# test3.net
KiCad netlist of a schematic drawn in Altium Designer
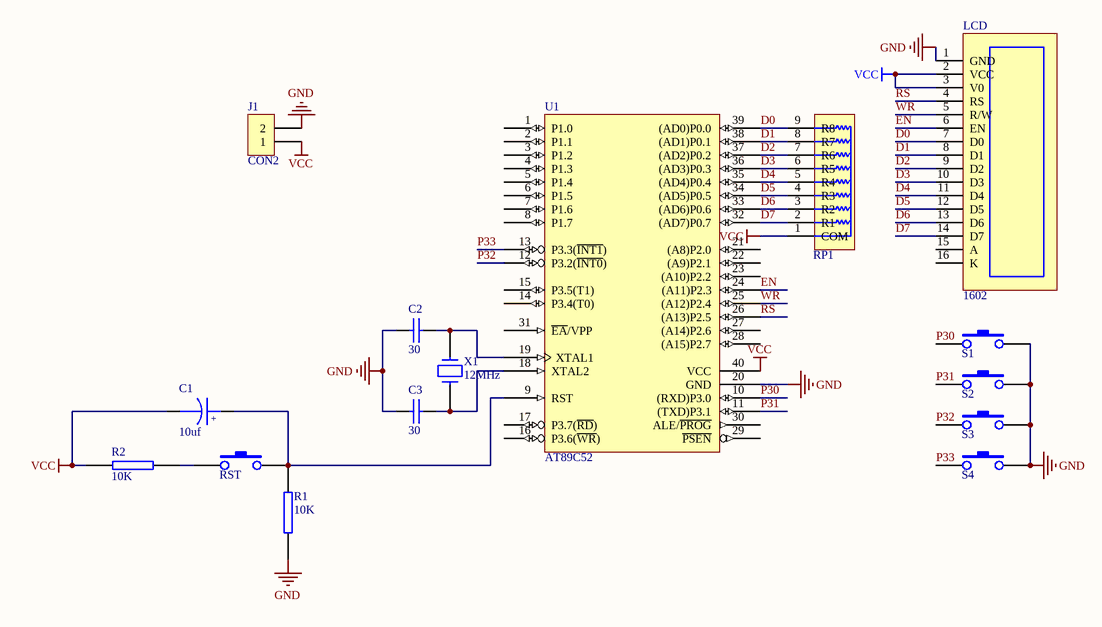
[diagram p0: test3.SchDoc]

(export (version "E")
  (design (tool "Eeschema 10.0.6"))
  (components
    (comp (ref "C1")
      (value "10uf")
      (footprint "C_SMT-5*5")
      (description "Capacitor")
      (libsource (lib "xinweidz") (part "电解电容"))
    )
    (comp (ref "C2")
      (value "30")
      (footprint "C0805")
      (description "Capacitor")
      (libsource (lib "*") (part "CAP"))
    )
    (comp (ref "C3")
      (value "30")
      (footprint "C0805")
      (description "Capacitor")
      (libsource (lib "*") (part "CAP"))
    )
    (comp (ref "J1")
      (value "CON2")
      (footprint "TC2")
      (description "Connector")
      (libsource (lib "51单片机最小系统.PcbDoc") (part "CON2"))
    )
    (comp (ref "LCD") (value "1602") (footprint "LCD1602") (libsource (lib "*") (part "LCM1602")))
    (comp (ref "R1") (value "10K") (footprint "C0805") (libsource (lib "*") (part "RES2")))
    (comp (ref "R2") (value "10K") (footprint "C0805") (libsource (lib "*") (part "RES2")))
    (comp (ref "RP1") (value "103") (footprint "R-9PIN") (libsource (lib "*") (part "RP8")))
    (comp (ref "RST")
      (value "SW-PB")
      (footprint "ANJIAN")
      (libsource (lib "51单片机最小系统.PcbDoc") (part "SW-PB"))
    )
    (comp (ref "S1") (value "SW-PB") (footprint "ANJIAN") (libsource (lib "51单片机最小系统.PcbDoc") (part "SW-PB")))
    (comp (ref "S2") (value "SW-PB") (footprint "ANJIAN") (libsource (lib "51单片机最小系统.PcbDoc") (part "SW-PB")))
    (comp (ref "S3") (value "SW-PB") (footprint "ANJIAN") (libsource (lib "51单片机最小系统.PcbDoc") (part "SW-PB")))
    (comp (ref "S4") (value "SW-PB") (footprint "ANJIAN") (libsource (lib "51单片机最小系统.PcbDoc") (part "SW-PB")))
    (comp (ref "U1")
      (value "AT89C52")
      (footprint "JINSUOZUO")
      (description "8-Bit Microcontroller with 4K Flash ROM")
      (libsource (lib "51单片机最小系统.PcbDoc") (part "AT89C51"))
    )
    (comp (ref "X1")
      (value "12MHz")
      (footprint "XTAL1")
      (description "Crystal")
      (libsource (lib "*") (part "CRYSTAL"))
    )
  )
  (nets
    (net (code "1") (name "/D0") (class "Default")
      (node (ref "LCD") (pin "7") (pinfunction "D0_7") (pintype "passive"))
      (node (ref "RP1") (pin "9") (pinfunction "R8_9") (pintype "passive"))
      (node (ref "U1") (pin "39") (pinfunction "(AD0)P0.0_39") (pintype "bidirectional"))
    )
    (net (code "2") (name "/D1") (class "Default")
      (node (ref "LCD") (pin "8") (pinfunction "D1_8") (pintype "passive"))
      (node (ref "RP1") (pin "8") (pinfunction "R7_8") (pintype "passive"))
      (node (ref "U1") (pin "38") (pinfunction "(AD1)P0.1_38") (pintype "bidirectional"))
    )
    (net (code "3") (name "/D2") (class "Default")
      (node (ref "LCD") (pin "9") (pinfunction "D2_9") (pintype "passive"))
      (node (ref "RP1") (pin "7") (pinfunction "R6_7") (pintype "passive"))
      (node (ref "U1") (pin "37") (pinfunction "(AD2)P0.2_37") (pintype "bidirectional"))
    )
    (net (code "4") (name "/D3") (class "Default")
      (node (ref "LCD") (pin "10") (pinfunction "D3_10") (pintype "passive"))
      (node (ref "RP1") (pin "6") (pinfunction "R5_6") (pintype "passive"))
      (node (ref "U1") (pin "36") (pinfunction "(AD3)P0.3_36") (pintype "bidirectional"))
    )
    (net (code "5") (name "/D4") (class "Default")
      (node (ref "LCD") (pin "11") (pinfunction "D4_11") (pintype "passive"))
      (node (ref "RP1") (pin "5") (pinfunction "R4_5") (pintype "passive"))
      (node (ref "U1") (pin "35") (pinfunction "(AD4)P0.4_35") (pintype "bidirectional"))
    )
    (net (code "6") (name "/D5") (class "Default")
      (node (ref "LCD") (pin "12") (pinfunction "D5_12") (pintype "passive"))
      (node (ref "RP1") (pin "4") (pinfunction "R3_4") (pintype "passive"))
      (node (ref "U1") (pin "34") (pinfunction "(AD5)P0.5_34") (pintype "bidirectional"))
    )
    (net (code "7") (name "/D6") (class "Default")
      (node (ref "LCD") (pin "13") (pinfunction "D6_13") (pintype "passive"))
      (node (ref "RP1") (pin "3") (pinfunction "R2_3") (pintype "passive"))
      (node (ref "U1") (pin "33") (pinfunction "(AD6)P0.6_33") (pintype "bidirectional"))
    )
    (net (code "8") (name "/D7") (class "Default")
      (node (ref "LCD") (pin "14") (pinfunction "D7_14") (pintype "passive"))
      (node (ref "RP1") (pin "2") (pinfunction "R1_2") (pintype "passive"))
      (node (ref "U1") (pin "32") (pinfunction "(AD7)P0.7_32") (pintype "bidirectional"))
    )
    (net (code "9") (name "/EN") (class "Default")
      (node (ref "LCD") (pin "6") (pinfunction "EN_6") (pintype "passive"))
      (node (ref "U1") (pin "24") (pinfunction "(A11)P2.3_24") (pintype "bidirectional"))
    )
    (net (code "10") (name "/P30") (class "Default")
      (node (ref "S1") (pin "1") (pinfunction "1_1") (pintype "passive"))
      (node (ref "U1") (pin "10") (pinfunction "(RXD)P3.0_10") (pintype "bidirectional"))
    )
    (net (code "11") (name "/P31") (class "Default")
      (node (ref "S2") (pin "1") (pinfunction "1_1") (pintype "passive"))
      (node (ref "U1") (pin "11") (pinfunction "(TXD)P3.1_11") (pintype "bidirectional"))
    )
    (net (code "12") (name "/P32") (class "Default")
      (node (ref "S3") (pin "1") (pinfunction "1_1") (pintype "passive"))
      (node (ref "U1") (pin "12") (pinfunction "P3.2(~{INT0})_12") (pintype "bidirectional"))
    )
    (net (code "13") (name "/P33") (class "Default")
      (node (ref "S4") (pin "1") (pinfunction "1_1") (pintype "passive"))
      (node (ref "U1") (pin "13") (pinfunction "P3.3(~{INT1})_13") (pintype "bidirectional"))
    )
    (net (code "14") (name "/RS") (class "Default")
      (node (ref "LCD") (pin "4") (pinfunction "RS_4") (pintype "passive"))
      (node (ref "U1") (pin "26") (pinfunction "(A13)P2.5_26") (pintype "bidirectional"))
    )
    (net (code "15") (name "/WR") (class "Default")
      (node (ref "LCD") (pin "5") (pinfunction "R/W_5") (pintype "passive"))
      (node (ref "U1") (pin "25") (pinfunction "(A12)P2.4_25") (pintype "bidirectional"))
    )
    (net (code "16") (name "GND") (class "Default")
      (node (ref "C2") (pin "2") (pinfunction "2_2") (pintype "passive"))
      (node (ref "C3") (pin "2") (pinfunction "2_2") (pintype "passive"))
      (node (ref "J1") (pin "2") (pinfunction "2_2") (pintype "passive"))
      (node (ref "LCD") (pin "1") (pinfunction "GND_1") (pintype "passive"))
      (node (ref "R1") (pin "2") (pinfunction "2_2") (pintype "passive"))
      (node (ref "S1") (pin "2") (pinfunction "2_2") (pintype "passive"))
      (node (ref "S2") (pin "2") (pinfunction "2_2") (pintype "passive"))
      (node (ref "S3") (pin "2") (pinfunction "2_2") (pintype "passive"))
      (node (ref "S4") (pin "2") (pinfunction "2_2") (pintype "passive"))
      (node (ref "U1") (pin "20") (pinfunction "GND_20") (pintype "power_in"))
    )
    (net (code "17") (name "Net-(R2-Pad2)") (class "Default")
      (node (ref "R2") (pin "2") (pinfunction "2_2") (pintype "passive"))
      (node (ref "RST") (pin "1") (pinfunction "1_1") (pintype "passive"))
    )
    (net (code "18") (name "Net-(U1-RST)") (class "Default")
      (node (ref "C1") (pin "2") (pinfunction "2_2") (pintype "passive"))
      (node (ref "R1") (pin "1") (pinfunction "1_1") (pintype "passive"))
      (node (ref "RST") (pin "2") (pinfunction "2_2") (pintype "passive"))
      (node (ref "U1") (pin "9") (pinfunction "RST_9") (pintype "input"))
    )
    (net (code "19") (name "Net-(U1-XTAL1)") (class "Default")
      (node (ref "C2") (pin "1") (pinfunction "1_1") (pintype "passive"))
      (node (ref "U1") (pin "19") (pinfunction "XTAL1_19") (pintype "input"))
      (node (ref "X1") (pin "1") (pinfunction "1_1") (pintype "passive"))
    )
    (net (code "20") (name "Net-(U1-XTAL2)") (class "Default")
      (node (ref "C3") (pin "1") (pinfunction "1_1") (pintype "passive"))
      (node (ref "U1") (pin "18") (pinfunction "XTAL2_18") (pintype "input"))
      (node (ref "X1") (pin "2") (pinfunction "2_2") (pintype "passive"))
    )
    (net (code "21") (name "VCC") (class "Default")
      (node (ref "C1") (pin "1") (pinfunction "1_1") (pintype "passive"))
      (node (ref "J1") (pin "1") (pinfunction "1_1") (pintype "passive"))
      (node (ref "LCD") (pin "2") (pinfunction "VCC_2") (pintype "passive"))
      (node (ref "LCD") (pin "3") (pinfunction "V0_3") (pintype "passive"))
      (node (ref "R2") (pin "1") (pinfunction "1_1") (pintype "passive"))
      (node (ref "RP1") (pin "1") (pinfunction "COM_1") (pintype "passive"))
      (node (ref "U1") (pin "40") (pinfunction "VCC_40") (pintype "power_in"))
    )
    (net (code "22") (name "unconnected-(LCD-A-Pad15)") (class "Default")
      (node (ref "LCD") (pin "15") (pinfunction "A_15") (pintype "passive"))
    )
    (net (code "23") (name "unconnected-(LCD-K-Pad16)") (class "Default")
      (node (ref "LCD") (pin "16") (pinfunction "K_16") (pintype "passive"))
    )
    (net (code "24") (name "unconnected-(U1-(A8)P2.0-Pad21)") (class "Default")
      (node (ref "U1") (pin "21") (pinfunction "(A8)P2.0_21") (pintype "bidirectional"))
    )
    (net (code "25") (name "unconnected-(U1-(A9)P2.1-Pad22)") (class "Default")
      (node (ref "U1") (pin "22") (pinfunction "(A9)P2.1_22") (pintype "bidirectional"))
    )
    (net (code "26") (name "unconnected-(U1-(A10)P2.2-Pad23)") (class "Default")
      (node (ref "U1") (pin "23") (pinfunction "(A10)P2.2_23") (pintype "bidirectional"))
    )
    (net (code "27") (name "unconnected-(U1-(A14)P2.6-Pad27)") (class "Default")
      (node (ref "U1") (pin "27") (pinfunction "(A14)P2.6_27") (pintype "bidirectional"))
    )
    (net (code "28") (name "unconnected-(U1-(A15)P2.7-Pad28)") (class "Default")
      (node (ref "U1") (pin "28") (pinfunction "(A15)P2.7_28") (pintype "bidirectional"))
    )
    (net (code "29") (name "unconnected-(U1-ALE{slash}~{PROG}-Pad30)") (class "Default")
      (node (ref "U1") (pin "30") (pinfunction "ALE/~{PROG}_30") (pintype "output"))
    )
    (net (code "30") (name "unconnected-(U1-P1.0-Pad1)") (class "Default")
      (node (ref "U1") (pin "1") (pinfunction "P1.0_1") (pintype "bidirectional"))
    )
    (net (code "31") (name "unconnected-(U1-P1.1-Pad2)") (class "Default")
      (node (ref "U1") (pin "2") (pinfunction "P1.1_2") (pintype "bidirectional"))
    )
    (net (code "32") (name "unconnected-(U1-P1.2-Pad3)") (class "Default")
      (node (ref "U1") (pin "3") (pinfunction "P1.2_3") (pintype "bidirectional"))
    )
    (net (code "33") (name "unconnected-(U1-P1.3-Pad4)") (class "Default")
      (node (ref "U1") (pin "4") (pinfunction "P1.3_4") (pintype "bidirectional"))
    )
    (net (code "34") (name "unconnected-(U1-P1.4-Pad5)") (class "Default")
      (node (ref "U1") (pin "5") (pinfunction "P1.4_5") (pintype "bidirectional"))
    )
    (net (code "35") (name "unconnected-(U1-P1.5-Pad6)") (class "Default")
      (node (ref "U1") (pin "6") (pinfunction "P1.5_6") (pintype "bidirectional"))
    )
    (net (code "36") (name "unconnected-(U1-P1.6-Pad7)") (class "Default")
      (node (ref "U1") (pin "7") (pinfunction "P1.6_7") (pintype "bidirectional"))
    )
    (net (code "37") (name "unconnected-(U1-P1.7-Pad8)") (class "Default")
      (node (ref "U1") (pin "8") (pinfunction "P1.7_8") (pintype "bidirectional"))
    )
    (net (code "38") (name "unconnected-(U1-P3.4(T0)-Pad14)") (class "Default")
      (node (ref "U1") (pin "14") (pinfunction "P3.4(T0)_14") (pintype "bidirectional"))
    )
    (net (code "39") (name "unconnected-(U1-P3.5(T1)-Pad15)") (class "Default")
      (node (ref "U1") (pin "15") (pinfunction "P3.5(T1)_15") (pintype "bidirectional"))
    )
    (net (code "40") (name "unconnected-(U1-P3.6(~{WR})-Pad16)") (class "Default")
      (node (ref "U1") (pin "16") (pinfunction "P3.6(~{WR})_16") (pintype "bidirectional"))
    )
    (net (code "41") (name "unconnected-(U1-P3.7(~{RD})-Pad17)") (class "Default")
      (node (ref "U1") (pin "17") (pinfunction "P3.7(~{RD})_17") (pintype "bidirectional"))
    )
    (net (code "42") (name "unconnected-(U1-~{EA}{slash}VPP-Pad31)") (class "Default")
      (node (ref "U1") (pin "31") (pinfunction "~{EA}/VPP_31") (pintype "input"))
    )
    (net (code "43") (name "unconnected-(U1-~{PSEN}-Pad29)") (class "Default")
      (node (ref "U1") (pin "29") (pinfunction "~{PSEN}_29") (pintype "output"))
    )
  )
)
